# GaN_Dead_Time.net
KiCad netlist of a schematic drawn in Altium Designer
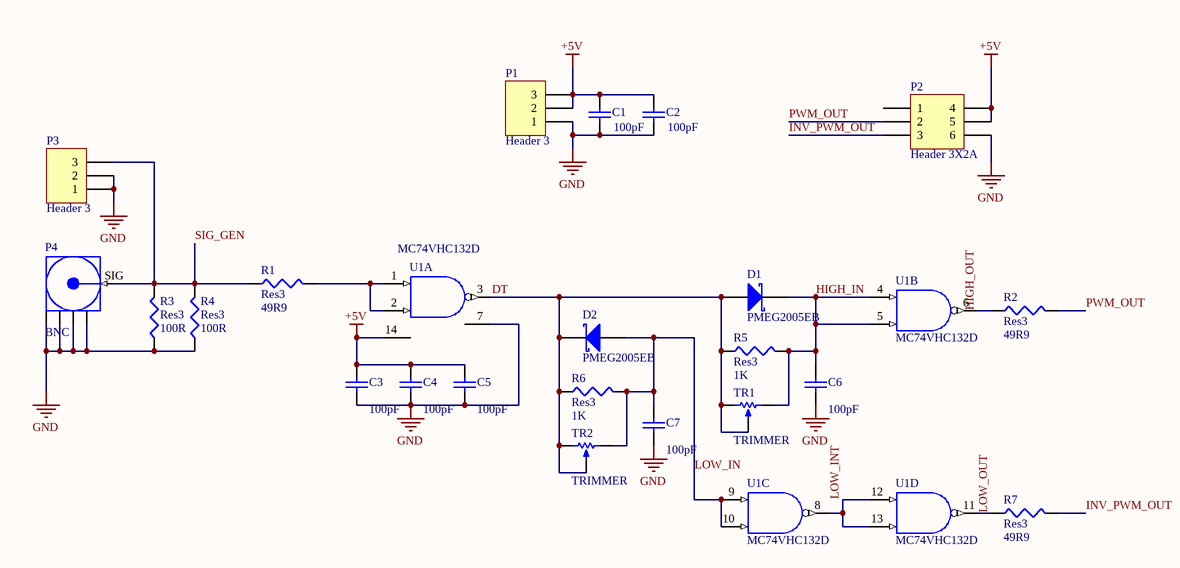
[diagram p0: GaN_Dead_Time.SchDoc]

(export (version "E")
  (design (tool "Eeschema 10.0.6"))
  (components
    (comp (ref "C1")
      (value "100pF")
      (footprint "1206 IPC Low Density")
      (description "Capacitor (Semiconductor SIM Model)")
      (fields (field (name "Comment") "Cap Semi") (field (name "PUBLISHER") "Altium Limited"))
      (libsource (lib "Miscellaneous Devices") (part "Cap Semi"))
    )
    (comp (ref "C2")
      (value "100pF")
      (footprint "1206 IPC Low Density")
      (description "Capacitor (Semiconductor SIM Model)")
      (fields (field (name "Comment") "Cap Semi") (field (name "PUBLISHER") "Altium Limited"))
      (libsource (lib "Miscellaneous Devices") (part "Cap Semi"))
    )
    (comp (ref "C3")
      (value "100pF")
      (footprint "0603 IPC Low Density")
      (description "Capacitor (Semiconductor SIM Model)")
      (fields (field (name "Comment") "Cap Semi") (field (name "PUBLISHER") "Altium Limited"))
      (libsource (lib "Miscellaneous Devices") (part "Cap Semi"))
    )
    (comp (ref "C4")
      (value "100pF")
      (footprint "0603 IPC Low Density")
      (description "Capacitor (Semiconductor SIM Model)")
      (fields (field (name "Comment") "Cap Semi") (field (name "PUBLISHER") "Altium Limited"))
      (libsource (lib "Miscellaneous Devices") (part "Cap Semi"))
    )
    (comp (ref "C5")
      (value "100pF")
      (footprint "0603 IPC Low Density")
      (description "Capacitor (Semiconductor SIM Model)")
      (fields (field (name "Comment") "Cap Semi") (field (name "PUBLISHER") "Altium Limited"))
      (libsource (lib "Miscellaneous Devices") (part "Cap Semi"))
    )
    (comp (ref "C6")
      (value "100pF")
      (footprint "0603 IPC Low Density")
      (description "Capacitor (Semiconductor SIM Model)")
      (fields (field (name "Comment") "Cap Semi") (field (name "PUBLISHER") "Altium Limited"))
      (libsource (lib "Miscellaneous Devices") (part "Cap Semi"))
    )
    (comp (ref "C7")
      (value "100pF")
      (footprint "0603 IPC Low Density")
      (description "Capacitor (Semiconductor SIM Model)")
      (fields (field (name "Comment") "Cap Semi") (field (name "PUBLISHER") "Altium Limited"))
      (libsource (lib "Miscellaneous Devices") (part "Cap Semi"))
    )
    (comp (ref "D1")
      (value "PMEG2005EB")
      (footprint "SOD-523")
      (description "Schottky Diode  SOD-523")
      (libsource (lib "GaN_Schlib") (part "PMEG2005EB"))
    )
    (comp (ref "D2")
      (value "PMEG2005EB")
      (footprint "SOD-523")
      (description "Schottky Diode  SOD-523")
      (libsource (lib "GaN_Schlib") (part "PMEG2005EB"))
    )
    (comp (ref "P1")
      (value "Header 3")
      (footprint "HDR1X3")
      (description "Header, 3-Pin")
      (fields (field (name "PUBLISHER") "Altium Limited"))
      (libsource (lib "Miscellaneous Connectors") (part "Header 3"))
    )
    (comp (ref "P2")
      (value "Header 3X2A")
      (footprint "HDR2X3_CEN")
      (description "Header, 3-Pin, Dual row")
      (fields (field (name "PUBLISHER") "Altium Limited"))
      (libsource (lib "Miscellaneous Connectors") (part "Header 3X2A"))
    )
    (comp (ref "P3")
      (value "Header 3")
      (footprint "HDR1X3")
      (description "Header, 3-Pin")
      (fields (field (name "PUBLISHER") "Altium Limited"))
      (libsource (lib "Miscellaneous Connectors") (part "Header 3"))
    )
    (comp (ref "P4")
      (value "BNC")
      (footprint "BNC")
      (description "Straight 50Ω Through Hole BNC Connector")
      (fields (field (name "PUBLISHER") "Altium Limited"))
      (libsource (lib "GaN_Schlib") (part "BNC"))
    )
    (comp (ref "R1")
      (value "Res3")
      (footprint "RESISTOR 0603")
      (description "Resistor")
      (fields (field (name "ALTIUM_VALUE") "49R9") (field (name "PUBLISHER") "Altium Limited"))
      (libsource (lib "Miscellaneous Devices") (part "Res3"))
    )
    (comp (ref "R2")
      (value "Res3")
      (footprint "RESISTOR 0603")
      (description "Resistor")
      (fields (field (name "ALTIUM_VALUE") "49R9") (field (name "PUBLISHER") "Altium Limited"))
      (libsource (lib "Miscellaneous Devices") (part "Res3"))
    )
    (comp (ref "R3")
      (value "Res3")
      (footprint "RESISTOR 1206")
      (description "Resistor")
      (fields (field (name "ALTIUM_VALUE") "100R") (field (name "PUBLISHER") "Altium Limited"))
      (libsource (lib "Miscellaneous Devices") (part "Res3"))
    )
    (comp (ref "R4")
      (value "Res3")
      (footprint "RESISTOR 1206")
      (description "Resistor")
      (fields (field (name "ALTIUM_VALUE") "100R") (field (name "PUBLISHER") "Altium Limited"))
      (libsource (lib "Miscellaneous Devices") (part "Res3"))
    )
    (comp (ref "R5")
      (value "Res3")
      (footprint "RESISTOR 0603")
      (description "Resistor")
      (fields (field (name "ALTIUM_VALUE") "1K") (field (name "PUBLISHER") "Altium Limited"))
      (libsource (lib "Miscellaneous Devices") (part "Res3"))
    )
    (comp (ref "R6")
      (value "Res3")
      (footprint "RESISTOR 0603")
      (description "Resistor")
      (fields (field (name "ALTIUM_VALUE") "1K") (field (name "PUBLISHER") "Altium Limited"))
      (libsource (lib "Miscellaneous Devices") (part "Res3"))
    )
    (comp (ref "R7")
      (value "Res3")
      (footprint "RESISTOR 0603")
      (description "Resistor")
      (fields (field (name "ALTIUM_VALUE") "49R9") (field (name "PUBLISHER") "Altium Limited"))
      (libsource (lib "Miscellaneous Devices") (part "Res3"))
    )
    (comp (ref "TR1")
      (value "TRIMMER")
      (footprint "3296W")
      (libsource (lib "GaN_Schlib") (part "TRIMMER 3296W"))
    )
    (comp (ref "TR2")
      (value "TRIMMER")
      (footprint "3296W")
      (libsource (lib "GaN_Schlib") (part "TRIMMER 3296W"))
    )
    (comp (ref "U1")
      (value "MC74VHC132D")
      (footprint "751A-03_M")
      (description "Quad 2-Input NAND Schmitt Trigger")
      (fields (field (name "PUBLISHER") "Altium Limited"))
      (libsource (lib "ON Semi Logic Gate") (part "MC74VHC132D"))
    )
  )
  (nets
    (net (code "1") (name "+5V") (class "Default")
      (node (ref "C1") (pin "2") (pinfunction "2_2") (pintype "passive"))
      (node (ref "C2") (pin "2") (pinfunction "2_2") (pintype "passive"))
      (node (ref "C3") (pin "2") (pinfunction "2_2") (pintype "passive"))
      (node (ref "C4") (pin "2") (pinfunction "2_2") (pintype "passive"))
      (node (ref "C5") (pin "2") (pinfunction "2_2") (pintype "passive"))
      (node (ref "P1") (pin "2") (pinfunction "2_2") (pintype "passive"))
      (node (ref "P1") (pin "3") (pinfunction "3_3") (pintype "passive"))
      (node (ref "P2") (pin "4") (pinfunction "4_4") (pintype "passive"))
      (node (ref "P2") (pin "5") (pinfunction "5_5") (pintype "passive"))
      (node (ref "U1") (pin "14") (pinfunction "VDD_14") (pintype "power_in"))
    )
    (net (code "2") (name "/DT") (class "Default")
      (node (ref "D1") (pin "1") (pinfunction "A_1") (pintype "passive"))
      (node (ref "D2") (pin "3") (pinfunction "K_3") (pintype "passive"))
      (node (ref "R5") (pin "1") (pinfunction "1_1") (pintype "passive"))
      (node (ref "R6") (pin "1") (pinfunction "1_1") (pintype "passive"))
      (node (ref "TR1") (pin "1") (pinfunction "TOP_1") (pintype "passive"))
      (node (ref "TR1") (pin "2") (pinfunction "TAP_2") (pintype "passive"))
      (node (ref "TR2") (pin "1") (pinfunction "TOP_1") (pintype "passive"))
      (node (ref "TR2") (pin "2") (pinfunction "TAP_2") (pintype "passive"))
      (node (ref "U1") (pin "3") (pinfunction "Y_3") (pintype "output"))
    )
    (net (code "3") (name "/HIGH_IN") (class "Default")
      (node (ref "C6") (pin "2") (pinfunction "2_2") (pintype "passive"))
      (node (ref "D1") (pin "3") (pinfunction "K_3") (pintype "passive"))
      (node (ref "R5") (pin "2") (pinfunction "2_2") (pintype "passive"))
      (node (ref "TR1") (pin "3") (pinfunction "BOT_3") (pintype "passive"))
      (node (ref "U1") (pin "4") (pinfunction "A_4") (pintype "input"))
      (node (ref "U1") (pin "5") (pinfunction "B_5") (pintype "input"))
    )
    (net (code "4") (name "/HIGH_OUT") (class "Default")
      (node (ref "R2") (pin "1") (pinfunction "1_1") (pintype "passive"))
      (node (ref "U1") (pin "6") (pinfunction "Y_6") (pintype "output"))
    )
    (net (code "5") (name "/INV_PWM_OUT") (class "Default")
      (node (ref "P2") (pin "3") (pinfunction "3_3") (pintype "passive"))
      (node (ref "R7") (pin "2") (pinfunction "2_2") (pintype "passive"))
    )
    (net (code "6") (name "/LOW_IN") (class "Default")
      (node (ref "C7") (pin "2") (pinfunction "2_2") (pintype "passive"))
      (node (ref "D2") (pin "1") (pinfunction "A_1") (pintype "passive"))
      (node (ref "R6") (pin "2") (pinfunction "2_2") (pintype "passive"))
      (node (ref "TR2") (pin "3") (pinfunction "BOT_3") (pintype "passive"))
      (node (ref "U1") (pin "10") (pinfunction "B_10") (pintype "input"))
      (node (ref "U1") (pin "9") (pinfunction "A_9") (pintype "input"))
    )
    (net (code "7") (name "/LOW_INT") (class "Default")
      (node (ref "U1") (pin "12") (pinfunction "A_12") (pintype "input"))
      (node (ref "U1") (pin "13") (pinfunction "B_13") (pintype "input"))
      (node (ref "U1") (pin "8") (pinfunction "Y_8") (pintype "output"))
    )
    (net (code "8") (name "/LOW_OUT") (class "Default")
      (node (ref "R7") (pin "1") (pinfunction "1_1") (pintype "passive"))
      (node (ref "U1") (pin "11") (pinfunction "Y_11") (pintype "output"))
    )
    (net (code "9") (name "/PWM_OUT") (class "Default")
      (node (ref "P2") (pin "2") (pinfunction "2_2") (pintype "passive"))
      (node (ref "R2") (pin "2") (pinfunction "2_2") (pintype "passive"))
    )
    (net (code "10") (name "/SIG_GEN") (class "Default")
      (node (ref "P3") (pin "3") (pinfunction "3_3") (pintype "passive"))
      (node (ref "P4") (pin "SIG") (pinfunction "Signal_SIG") (pintype "input"))
      (node (ref "R1") (pin "1") (pinfunction "1_1") (pintype "passive"))
      (node (ref "R3") (pin "2") (pinfunction "2_2") (pintype "passive"))
      (node (ref "R4") (pin "2") (pinfunction "2_2") (pintype "passive"))
    )
    (net (code "11") (name "GND") (class "Default")
      (node (ref "C1") (pin "1") (pinfunction "1_1") (pintype "passive"))
      (node (ref "C2") (pin "1") (pinfunction "1_1") (pintype "passive"))
      (node (ref "C3") (pin "1") (pinfunction "1_1") (pintype "passive"))
      (node (ref "C4") (pin "1") (pinfunction "1_1") (pintype "passive"))
      (node (ref "C5") (pin "1") (pinfunction "1_1") (pintype "passive"))
      (node (ref "C6") (pin "1") (pinfunction "1_1") (pintype "passive"))
      (node (ref "C7") (pin "1") (pinfunction "1_1") (pintype "passive"))
      (node (ref "P1") (pin "1") (pinfunction "1_1") (pintype "passive"))
      (node (ref "P2") (pin "6") (pinfunction "6_6") (pintype "passive"))
      (node (ref "P3") (pin "1") (pinfunction "1_1") (pintype "passive"))
      (node (ref "P3") (pin "2") (pinfunction "2_2") (pintype "passive"))
      (node (ref "P4") (pin "GND") (pinfunction "GND_GND") (pintype "power_in"))
      (node (ref "R3") (pin "1") (pinfunction "1_1") (pintype "passive"))
      (node (ref "R4") (pin "1") (pinfunction "1_1") (pintype "passive"))
      (node (ref "U1") (pin "7") (pinfunction "GND_7") (pintype "power_in"))
    )
    (net (code "12") (name "Net-(U1A-A)") (class "Default")
      (node (ref "R1") (pin "2") (pinfunction "2_2") (pintype "passive"))
      (node (ref "U1") (pin "1") (pinfunction "A_1") (pintype "input"))
      (node (ref "U1") (pin "2") (pinfunction "B_2") (pintype "input"))
    )
    (net (code "13") (name "unconnected-(P2-Pad1)") (class "Default")
      (node (ref "P2") (pin "1") (pinfunction "1_1") (pintype "passive"))
    )
  )
)
